# NG2094_CENTER_OV9782.net
KiCad netlist of a schematic drawn in Altium Designer
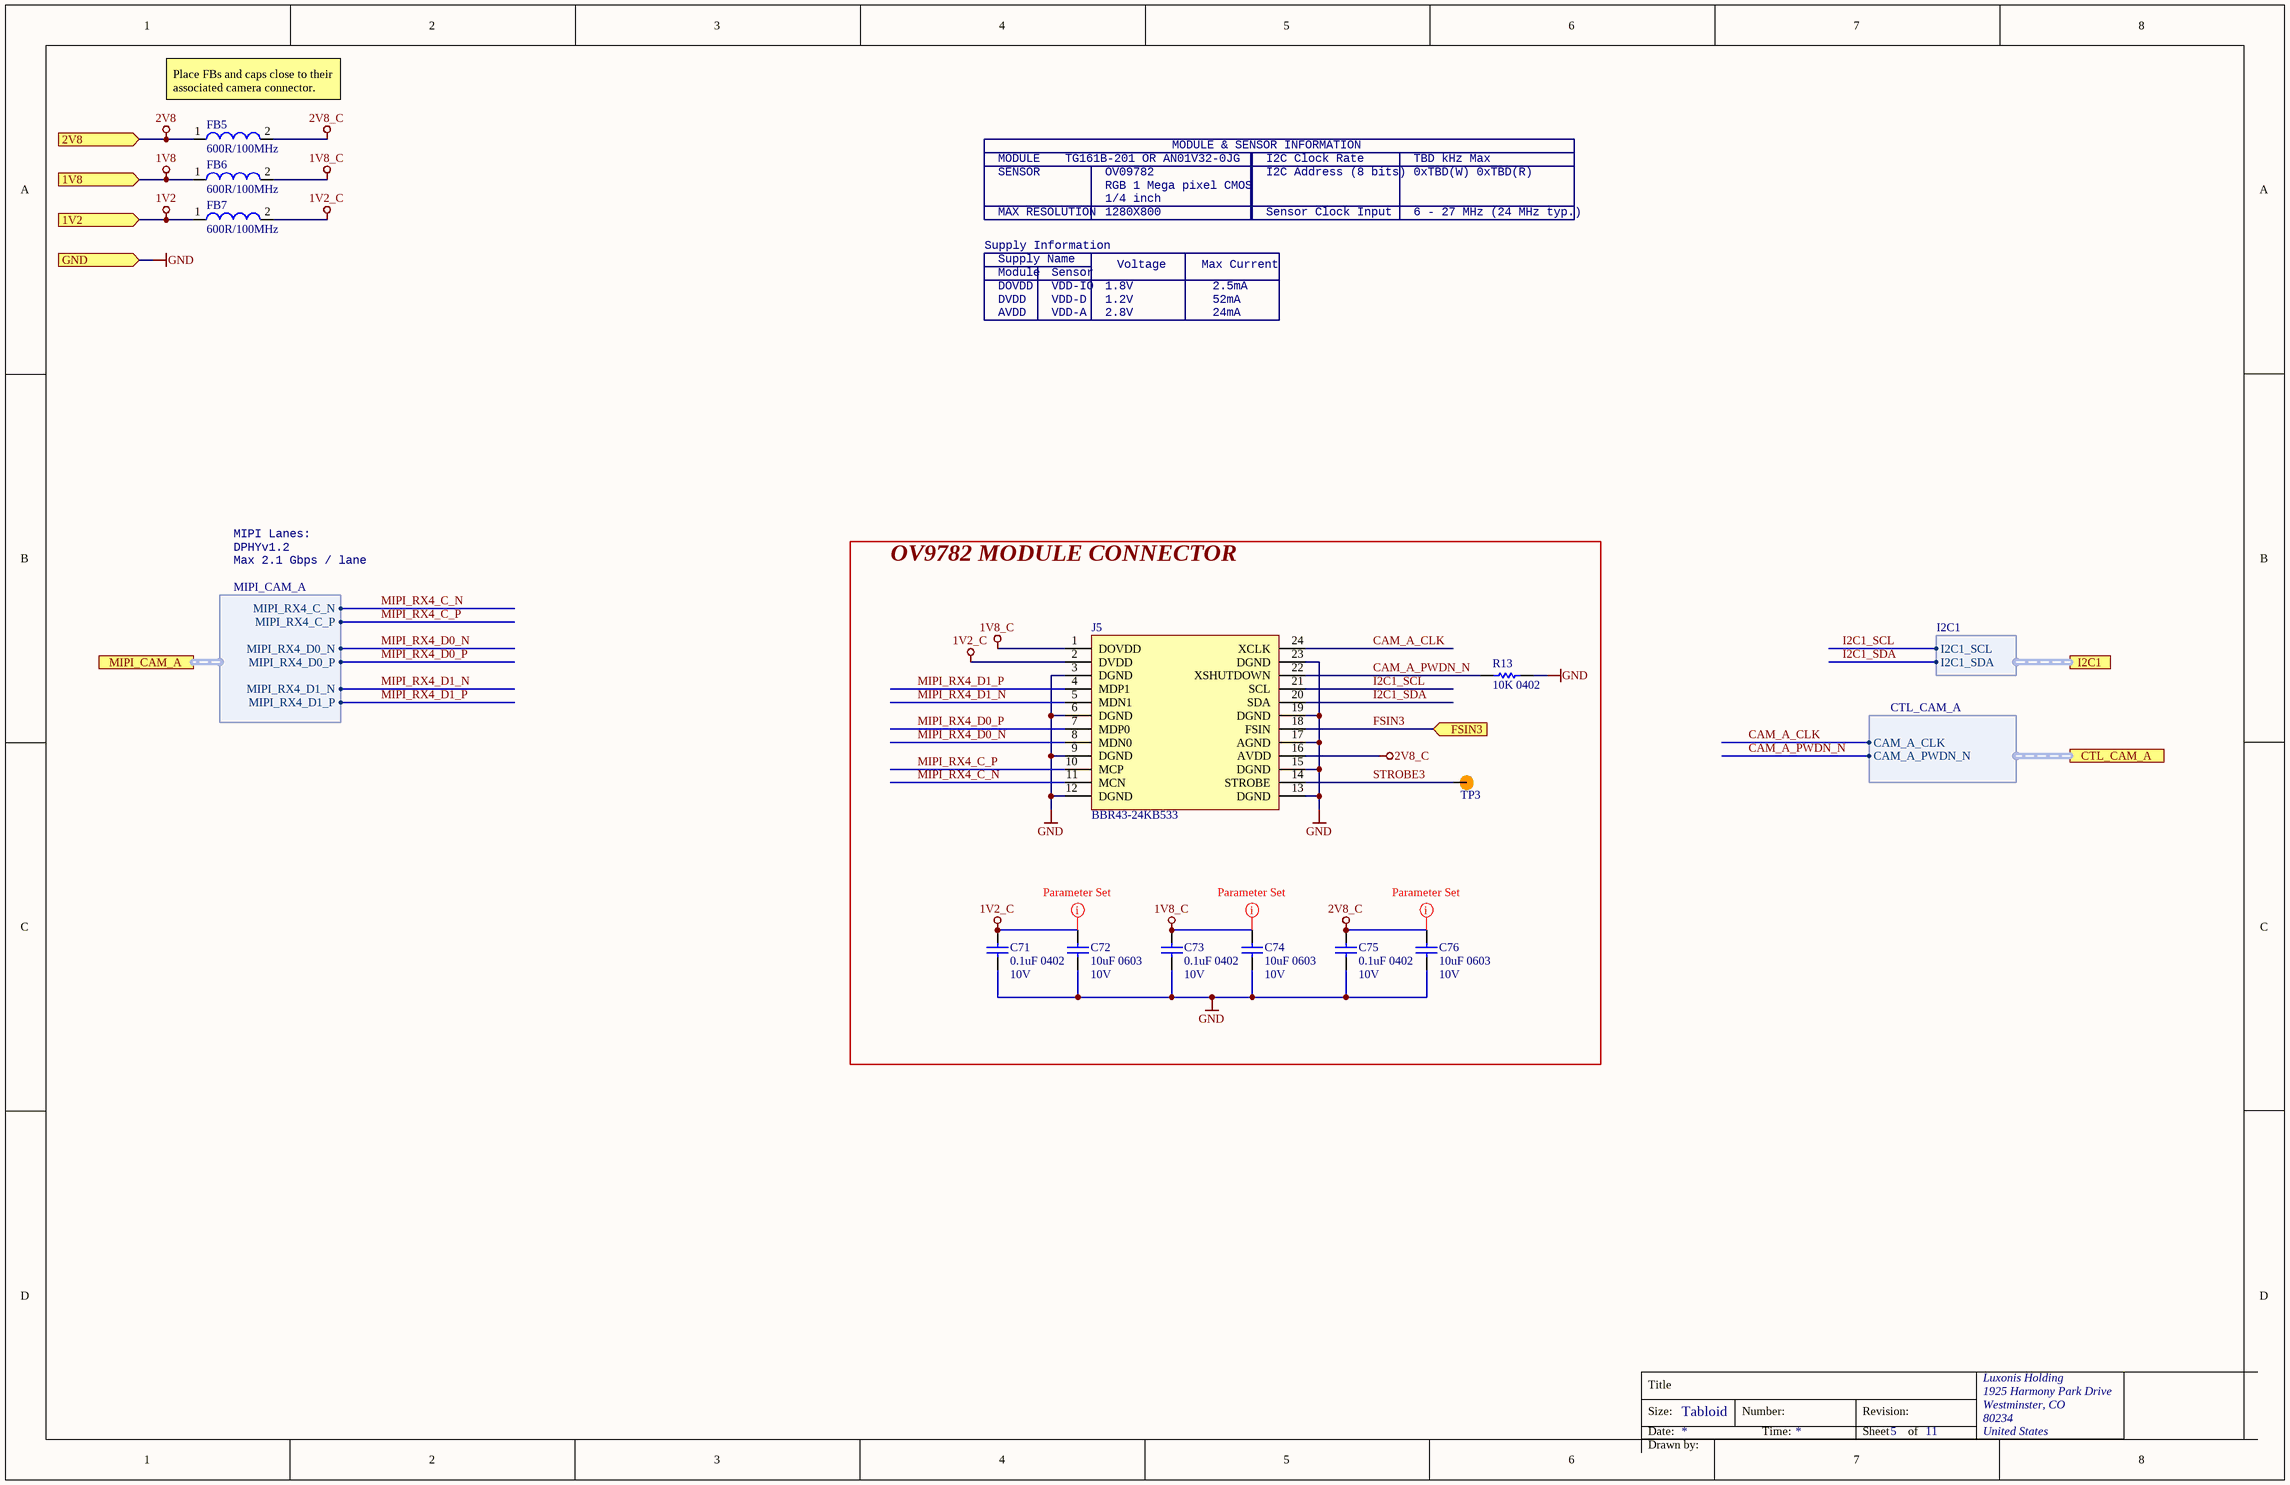
[diagram p0: NG2094_CENTER_OV9782.SchDoc]

(export (version "E")
  (design (tool "Eeschema 10.0.6"))
  (components
    (comp (ref "C71")
      (value "0.1uF 0402")
      (footprint "CAP_Altium_Vault_Generic:CAPC0402(1005)70_L")
      (description "CAP CER 0.1UF 10V X7R 0402 5%")
      (fields (field (name "TOLERANCE") "5%") (field (name "VOLTAGE RATING") "10V"))
      (libsource (lib "LuxonisMaster") (part "GRM155R71A104JA01D"))
    )
    (comp (ref "C72")
      (value "10uF 0603")
      (footprint "CAP_Altium_Vault_Generic:CAPC0603(1608)100_L")
      (description "CAP CER 10UF 10V X5R 0603 20%")
      (fields (field (name "TOLERANCE") "20%") (field (name "VOLTAGE RATING") "10V"))
      (libsource (lib "LuxonisMaster") (part "GRM188R61A106ME69D"))
    )
    (comp (ref "C73")
      (value "0.1uF 0402")
      (footprint "CAP_Altium_Vault_Generic:CAPC0402(1005)70_L")
      (description "CAP CER 0.1UF 10V X7R 0402 5%")
      (fields (field (name "TOLERANCE") "5%") (field (name "VOLTAGE RATING") "10V"))
      (libsource (lib "LuxonisMaster") (part "GRM155R71A104JA01D"))
    )
    (comp (ref "C74")
      (value "10uF 0603")
      (footprint "CAP_Altium_Vault_Generic:CAPC0603(1608)100_L")
      (description "CAP CER 10UF 10V X5R 0603 20%")
      (fields (field (name "TOLERANCE") "20%") (field (name "VOLTAGE RATING") "10V"))
      (libsource (lib "LuxonisMaster") (part "GRM188R61A106ME69D"))
    )
    (comp (ref "C75")
      (value "0.1uF 0402")
      (footprint "CAP_Altium_Vault_Generic:CAPC0402(1005)70_L")
      (description "CAP CER 0.1UF 10V X7R 0402 5%")
      (fields (field (name "TOLERANCE") "5%") (field (name "VOLTAGE RATING") "10V"))
      (libsource (lib "LuxonisMaster") (part "GRM155R71A104JA01D"))
    )
    (comp (ref "C76")
      (value "10uF 0603")
      (footprint "CAP_Altium_Vault_Generic:CAPC0603(1608)100_L")
      (description "CAP CER 10UF 10V X5R 0603 20%")
      (fields (field (name "TOLERANCE") "20%") (field (name "VOLTAGE RATING") "10V"))
      (libsource (lib "LuxonisMaster") (part "GRM188R61A106ME69D"))
    )
    (comp (ref "FB5")
      (value "600R/100MHz")
      (footprint "LuxonisMaster:2508056017Y2")
      (description "FERRITE BEAD, 0.1OHM, 2A, 0805, 600R/100MHz")
      (fields (field (name "TOLERANCE") "25%"))
      (libsource (lib "LuxonisMaster") (part "2508056017Y2"))
    )
    (comp (ref "FB6")
      (value "600R/100MHz")
      (footprint "LuxonisMaster:2508056017Y2")
      (description "FERRITE BEAD, 0.1OHM, 2A, 0805, 600R/100MHz")
      (fields (field (name "TOLERANCE") "25%"))
      (libsource (lib "LuxonisMaster") (part "2508056017Y2"))
    )
    (comp (ref "FB7")
      (value "600R/100MHz")
      (footprint "LuxonisMaster:2508056017Y2")
      (description "FERRITE BEAD, 0.1OHM, 2A, 0805, 600R/100MHz")
      (fields (field (name "TOLERANCE") "25%"))
      (libsource (lib "LuxonisMaster") (part "2508056017Y2"))
    )
    (comp (ref "J5")
      (value "BBR43-24KB533")
      (footprint "TG161B-201_W")
      (description "CONN 24 way, 2 row board to board connector SMD")
      (libsource (lib "LuxonisMaster") (part "TG161B-201_Connector"))
    )
    (comp (ref "R13")
      (value "10K 0402")
      (footprint "RES_Altium_Vault_Generic:RESC0402(1005)_L")
      (fields (field (name "TOLERANCE") "1%"))
      (libsource (lib "LuxonisMaster") (part "RC0402FR-1310KL"))
    )
    (comp (ref "TP3")
      (value "TP100_200_NS")
      (footprint "LuxonisMaster:TP100_200_NS")
      (libsource (lib "LuxonisMaster") (part "TEST_POINT"))
    )
  )
  (nets
    (net (code "4") (name "/CAM_A_CLK") (class "Default")
      (node (ref "J5") (pin "24") (pinfunction "XCLK_24") (pintype "passive"))
    )
    (net (code "5") (name "/CAM_A_PWDN_N") (class "Default")
      (node (ref "J5") (pin "22") (pinfunction "XSHUTDOWN_22") (pintype "passive"))
      (node (ref "R13") (pin "1") (pinfunction "1_1") (pintype "passive"))
    )
    (net (code "6") (name "/FSIN3") (class "Default")
      (node (ref "J5") (pin "18") (pinfunction "FSIN_18") (pintype "passive"))
    )
    (net (code "7") (name "/I2C1_SCL") (class "Default")
      (node (ref "J5") (pin "21") (pinfunction "SCL_21") (pintype "passive"))
    )
    (net (code "8") (name "/I2C1_SDA") (class "Default")
      (node (ref "J5") (pin "20") (pinfunction "SDA_20") (pintype "passive"))
    )
    (net (code "9") (name "/MIPI_RX4_C_N") (class "Default")
      (node (ref "J5") (pin "11") (pinfunction "MCN_11") (pintype "passive"))
    )
    (net (code "10") (name "/MIPI_RX4_C_P") (class "Default")
      (node (ref "J5") (pin "10") (pinfunction "MCP_10") (pintype "passive"))
    )
    (net (code "11") (name "/MIPI_RX4_D0_N") (class "Default")
      (node (ref "J5") (pin "8") (pinfunction "MDN0_8") (pintype "passive"))
    )
    (net (code "12") (name "/MIPI_RX4_D0_P") (class "Default")
      (node (ref "J5") (pin "7") (pinfunction "MDP0_7") (pintype "passive"))
    )
    (net (code "13") (name "/MIPI_RX4_D1_N") (class "Default")
      (node (ref "J5") (pin "5") (pinfunction "MDN1_5") (pintype "passive"))
    )
    (net (code "14") (name "/MIPI_RX4_D1_P") (class "Default")
      (node (ref "J5") (pin "4") (pinfunction "MDP1_4") (pintype "passive"))
    )
    (net (code "15") (name "/STROBE3") (class "Default")
      (node (ref "J5") (pin "14") (pinfunction "STROBE_14") (pintype "passive"))
      (node (ref "TP3") (pin "1") (pintype "passive"))
    )
    (net (code "19") (name "1V2") (class "Default")
      (node (ref "FB7") (pin "1") (pinfunction "1_1") (pintype "passive"))
    )
    (net (code "20") (name "1V2_C") (class "Default")
      (node (ref "C71") (pin "2") (pinfunction "2_2") (pintype "passive"))
      (node (ref "C72") (pin "2") (pinfunction "2_2") (pintype "passive"))
      (node (ref "FB7") (pin "2") (pinfunction "2_2") (pintype "passive"))
      (node (ref "J5") (pin "2") (pinfunction "DVDD_2") (pintype "passive"))
    )
    (net (code "21") (name "1V8") (class "Default")
      (node (ref "FB6") (pin "1") (pinfunction "1_1") (pintype "passive"))
    )
    (net (code "22") (name "1V8_C") (class "Default")
      (node (ref "C73") (pin "2") (pinfunction "2_2") (pintype "passive"))
      (node (ref "C74") (pin "2") (pinfunction "2_2") (pintype "passive"))
      (node (ref "FB6") (pin "2") (pinfunction "2_2") (pintype "passive"))
      (node (ref "J5") (pin "1") (pinfunction "DOVDD_1") (pintype "passive"))
    )
    (net (code "23") (name "2V8") (class "Default")
      (node (ref "FB5") (pin "1") (pinfunction "1_1") (pintype "passive"))
    )
    (net (code "24") (name "2V8_C") (class "Default")
      (node (ref "C75") (pin "2") (pinfunction "2_2") (pintype "passive"))
      (node (ref "C76") (pin "2") (pinfunction "2_2") (pintype "passive"))
      (node (ref "FB5") (pin "2") (pinfunction "2_2") (pintype "passive"))
      (node (ref "J5") (pin "16") (pinfunction "AVDD_16") (pintype "passive"))
    )
    (net (code "25") (name "GND") (class "Default")
      (node (ref "C71") (pin "1") (pinfunction "1_1") (pintype "passive"))
      (node (ref "C72") (pin "1") (pinfunction "1_1") (pintype "passive"))
      (node (ref "C73") (pin "1") (pinfunction "1_1") (pintype "passive"))
      (node (ref "C74") (pin "1") (pinfunction "1_1") (pintype "passive"))
      (node (ref "C75") (pin "1") (pinfunction "1_1") (pintype "passive"))
      (node (ref "C76") (pin "1") (pinfunction "1_1") (pintype "passive"))
      (node (ref "J5") (pin "12") (pinfunction "DGND_12") (pintype "passive"))
      (node (ref "J5") (pin "13") (pinfunction "DGND_13") (pintype "passive"))
      (node (ref "J5") (pin "15") (pinfunction "DGND_15") (pintype "passive"))
      (node (ref "J5") (pin "17") (pinfunction "AGND_17") (pintype "passive"))
      (node (ref "J5") (pin "19") (pinfunction "DGND_19") (pintype "passive"))
      (node (ref "J5") (pin "23") (pinfunction "DGND_23") (pintype "passive"))
      (node (ref "J5") (pin "3") (pinfunction "DGND_3") (pintype "passive"))
      (node (ref "J5") (pin "6") (pinfunction "DGND_6") (pintype "passive"))
      (node (ref "J5") (pin "9") (pinfunction "DGND_9") (pintype "passive"))
      (node (ref "R13") (pin "2") (pinfunction "2_2") (pintype "passive"))
    )
  )
)
